# 211_MLL-Range-Extender-CAT5_v0016.net
KiCad netlist of a schematic drawn in EAGLE
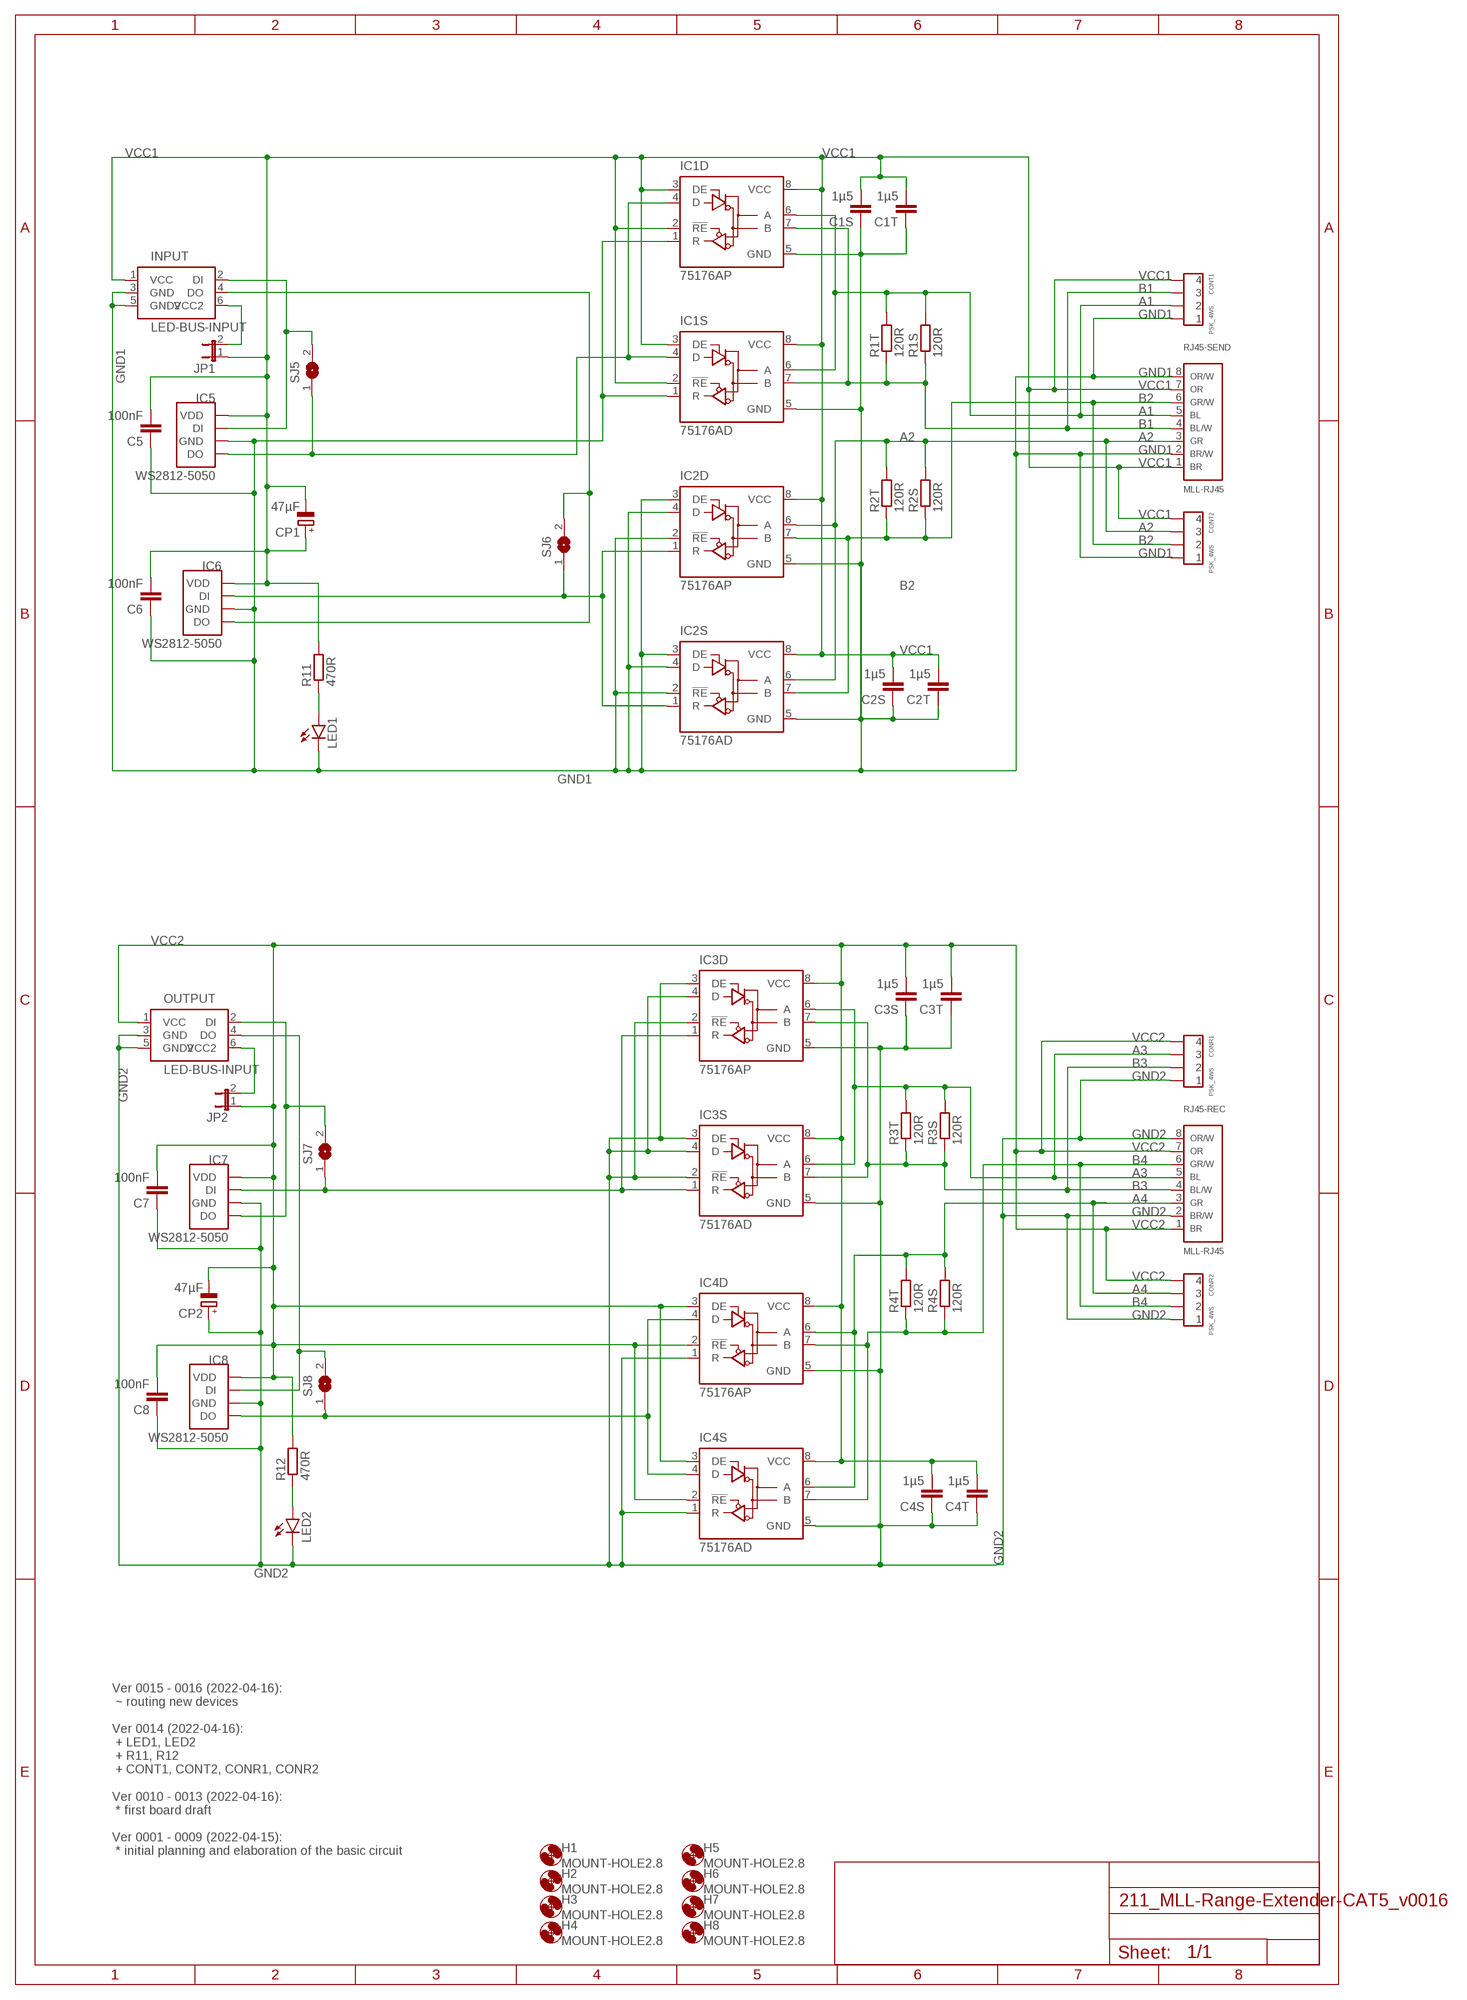
[diagram p0: schematic, sheet 1]

(export (version "E")
  (design (tool "Eeschema 10.0.6"))
  (components
    (comp (ref "C1S")
      (value "1µ5")
      (footprint "eagle-import:C1210")
      (libsource (lib "eagle-import") (part "C-EUC1210"))
    )
    (comp (ref "C1T")
      (value "1µ5")
      (footprint "eagle-import:C050-025X075")
      (libsource (lib "eagle-import") (part "C-EU050-025X075"))
    )
    (comp (ref "C2S")
      (value "1µ5")
      (footprint "eagle-import:C1210")
      (libsource (lib "eagle-import") (part "C-EUC1210"))
    )
    (comp (ref "C2T")
      (value "1µ5")
      (footprint "eagle-import:C050-025X075")
      (libsource (lib "eagle-import") (part "C-EU050-025X075"))
    )
    (comp (ref "C3S")
      (value "1µ5")
      (footprint "eagle-import:C1210")
      (libsource (lib "eagle-import") (part "C-EUC1210"))
    )
    (comp (ref "C3T")
      (value "1µ5")
      (footprint "eagle-import:C050-025X075")
      (libsource (lib "eagle-import") (part "C-EU050-025X075"))
    )
    (comp (ref "C4S")
      (value "1µ5")
      (footprint "eagle-import:C1210")
      (libsource (lib "eagle-import") (part "C-EUC1210"))
    )
    (comp (ref "C4T")
      (value "1µ5")
      (footprint "eagle-import:C050-025X075")
      (libsource (lib "eagle-import") (part "C-EU050-025X075"))
    )
    (comp (ref "C5")
      (value "100nF")
      (footprint "eagle-import:C025-025X050")
      (libsource (lib "eagle-import") (part "C-EU025-025X050"))
    )
    (comp (ref "C6")
      (value "100nF")
      (footprint "eagle-import:C025-025X050")
      (libsource (lib "eagle-import") (part "C-EU025-025X050"))
    )
    (comp (ref "C7")
      (value "100nF")
      (footprint "eagle-import:C025-025X050")
      (libsource (lib "eagle-import") (part "C-EU025-025X050"))
    )
    (comp (ref "C8")
      (value "100nF")
      (footprint "eagle-import:C025-025X050")
      (libsource (lib "eagle-import") (part "C-EU025-025X050"))
    )
    (comp (ref "CONR1")
      (value "PSK_4WS")
      (footprint "eagle-import:PSSW4-SHORT")
      (libsource (lib "eagle-import") (part "PSK_4WS"))
    )
    (comp (ref "CONR2")
      (value "PSK_4WS")
      (footprint "eagle-import:PSSW4-SHORT")
      (libsource (lib "eagle-import") (part "PSK_4WS"))
    )
    (comp (ref "CONT1")
      (value "PSK_4WS")
      (footprint "eagle-import:PSSW4-SHORT")
      (libsource (lib "eagle-import") (part "PSK_4WS"))
    )
    (comp (ref "CONT2")
      (value "PSK_4WS")
      (footprint "eagle-import:PSSW4-SHORT")
      (libsource (lib "eagle-import") (part "PSK_4WS"))
    )
    (comp (ref "CP1")
      (value "47µF")
      (footprint "eagle-import:E2-5")
      (libsource (lib "eagle-import") (part "CPOL-EUE2-5"))
    )
    (comp (ref "CP2")
      (value "47µF")
      (footprint "eagle-import:E2-5")
      (libsource (lib "eagle-import") (part "CPOL-EUE2-5"))
    )
    (comp (ref "H1")
      (value "MOUNT-HOLE2.8")
      (footprint "eagle-import:2,8")
      (libsource (lib "eagle-import") (part "MOUNT-HOLE2.8"))
    )
    (comp (ref "H2")
      (value "MOUNT-HOLE2.8")
      (footprint "eagle-import:2,8")
      (libsource (lib "eagle-import") (part "MOUNT-HOLE2.8"))
    )
    (comp (ref "H3")
      (value "MOUNT-HOLE2.8")
      (footprint "eagle-import:2,8")
      (libsource (lib "eagle-import") (part "MOUNT-HOLE2.8"))
    )
    (comp (ref "H4")
      (value "MOUNT-HOLE2.8")
      (footprint "eagle-import:2,8")
      (libsource (lib "eagle-import") (part "MOUNT-HOLE2.8"))
    )
    (comp (ref "H5")
      (value "MOUNT-HOLE2.8")
      (footprint "eagle-import:2,8")
      (libsource (lib "eagle-import") (part "MOUNT-HOLE2.8"))
    )
    (comp (ref "H6")
      (value "MOUNT-HOLE2.8")
      (footprint "eagle-import:2,8")
      (libsource (lib "eagle-import") (part "MOUNT-HOLE2.8"))
    )
    (comp (ref "H7")
      (value "MOUNT-HOLE2.8")
      (footprint "eagle-import:2,8")
      (libsource (lib "eagle-import") (part "MOUNT-HOLE2.8"))
    )
    (comp (ref "H8")
      (value "MOUNT-HOLE2.8")
      (footprint "eagle-import:2,8")
      (libsource (lib "eagle-import") (part "MOUNT-HOLE2.8"))
    )
    (comp (ref "IC1D")
      (value "75176AP")
      (footprint "eagle-import:DIL08")
      (libsource (lib "eagle-import") (part "75176AP"))
    )
    (comp (ref "IC1S")
      (value "75176AD")
      (footprint "eagle-import:D_R-PDSO-G8")
      (libsource (lib "eagle-import") (part "75176AD"))
    )
    (comp (ref "IC2D")
      (value "75176AP")
      (footprint "eagle-import:DIL08")
      (libsource (lib "eagle-import") (part "75176AP"))
    )
    (comp (ref "IC2S")
      (value "75176AD")
      (footprint "eagle-import:D_R-PDSO-G8")
      (libsource (lib "eagle-import") (part "75176AD"))
    )
    (comp (ref "IC3D")
      (value "75176AP")
      (footprint "eagle-import:DIL08")
      (libsource (lib "eagle-import") (part "75176AP"))
    )
    (comp (ref "IC3S")
      (value "75176AD")
      (footprint "eagle-import:D_R-PDSO-G8")
      (libsource (lib "eagle-import") (part "75176AD"))
    )
    (comp (ref "IC4D")
      (value "75176AP")
      (footprint "eagle-import:DIL08")
      (libsource (lib "eagle-import") (part "75176AP"))
    )
    (comp (ref "IC4S")
      (value "75176AD")
      (footprint "eagle-import:D_R-PDSO-G8")
      (libsource (lib "eagle-import") (part "75176AD"))
    )
    (comp (ref "IC5")
      (value "WS2812-5050")
      (footprint "eagle-import:5050")
      (libsource (lib "eagle-import") (part "WS2812-5050"))
    )
    (comp (ref "IC6")
      (value "WS2812-5050")
      (footprint "eagle-import:5050")
      (libsource (lib "eagle-import") (part "WS2812-5050"))
    )
    (comp (ref "IC7")
      (value "WS2812-5050")
      (footprint "eagle-import:5050")
      (libsource (lib "eagle-import") (part "WS2812-5050"))
    )
    (comp (ref "IC8")
      (value "WS2812-5050")
      (footprint "eagle-import:5050")
      (libsource (lib "eagle-import") (part "WS2812-5050"))
    )
    (comp (ref "INPUT")
      (value "LED-BUS-INPUT")
      (footprint "eagle-import:IDC6")
      (libsource (lib "eagle-import") (part "LED-BUS-INPUT"))
    )
    (comp (ref "JP1")
      (value "JP1E")
      (footprint "eagle-import:JP1")
      (libsource (lib "eagle-import") (part "JP1E"))
    )
    (comp (ref "JP2")
      (value "JP1E")
      (footprint "eagle-import:JP1")
      (libsource (lib "eagle-import") (part "JP1E"))
    )
    (comp (ref "LED1")
      (value "LED3MM")
      (footprint "eagle-import:LED3MM")
      (libsource (lib "eagle-import") (part "LED3MM"))
    )
    (comp (ref "LED2")
      (value "LED3MM")
      (footprint "eagle-import:LED3MM")
      (libsource (lib "eagle-import") (part "LED3MM"))
    )
    (comp (ref "OUTPUT")
      (value "LED-BUS-INPUT")
      (footprint "eagle-import:IDC6")
      (libsource (lib "eagle-import") (part "LED-BUS-INPUT"))
    )
    (comp (ref "R1S")
      (value "120R")
      (footprint "eagle-import:R1210")
      (libsource (lib "eagle-import") (part "R-EU_R1210"))
    )
    (comp (ref "R1T")
      (value "120R")
      (footprint "eagle-import:0207_10")
      (libsource (lib "eagle-import") (part "R-EU_0207/10"))
    )
    (comp (ref "R2S")
      (value "120R")
      (footprint "eagle-import:R1210")
      (libsource (lib "eagle-import") (part "R-EU_R1210"))
    )
    (comp (ref "R2T")
      (value "120R")
      (footprint "eagle-import:0207_10")
      (libsource (lib "eagle-import") (part "R-EU_0207/10"))
    )
    (comp (ref "R3S")
      (value "120R")
      (footprint "eagle-import:R1210")
      (libsource (lib "eagle-import") (part "R-EU_R1210"))
    )
    (comp (ref "R3T")
      (value "120R")
      (footprint "eagle-import:0207_10")
      (libsource (lib "eagle-import") (part "R-EU_0207/10"))
    )
    (comp (ref "R4S")
      (value "120R")
      (footprint "eagle-import:R1210")
      (libsource (lib "eagle-import") (part "R-EU_R1210"))
    )
    (comp (ref "R4T")
      (value "120R")
      (footprint "eagle-import:0207_10")
      (libsource (lib "eagle-import") (part "R-EU_0207/10"))
    )
    (comp (ref "R11")
      (value "470R")
      (footprint "eagle-import:0207_10")
      (libsource (lib "eagle-import") (part "R-EU_0207/10"))
    )
    (comp (ref "R12")
      (value "470R")
      (footprint "eagle-import:0207_10")
      (libsource (lib "eagle-import") (part "R-EU_0207/10"))
    )
    (comp (ref "RJ45-REC")
      (value "MLL-RJ45")
      (footprint "eagle-import:RJ45_U")
      (libsource (lib "eagle-import") (part "MLL-RJ45"))
    )
    (comp (ref "RJ45-SEND")
      (value "MLL-RJ45")
      (footprint "eagle-import:RJ45_U")
      (libsource (lib "eagle-import") (part "MLL-RJ45"))
    )
    (comp (ref "SJ5") (value "SJ") (footprint "eagle-import:SJ") (libsource (lib "eagle-import") (part "SJ")))
    (comp (ref "SJ6") (value "SJ") (footprint "eagle-import:SJ") (libsource (lib "eagle-import") (part "SJ")))
    (comp (ref "SJ7") (value "SJ") (footprint "eagle-import:SJ") (libsource (lib "eagle-import") (part "SJ")))
    (comp (ref "SJ8") (value "SJ") (footprint "eagle-import:SJ") (libsource (lib "eagle-import") (part "SJ")))
  )
  (nets
    (net (code "1") (name "/A1") (class "Default")
      (node (ref "CONT1") (pin "P$2") (pinfunction "2_P$2") (pintype "bidirectional"))
      (node (ref "IC1D") (pin "6") (pinfunction "A_6") (pintype "output"))
      (node (ref "IC1S") (pin "6") (pinfunction "A_6") (pintype "output"))
      (node (ref "R1S") (pin "2") (pinfunction "2_2") (pintype "passive"))
      (node (ref "R1T") (pin "2") (pinfunction "2_2") (pintype "passive"))
      (node (ref "RJ45-SEND") (pin "5") (pinfunction "BLUE_5") (pintype "bidirectional"))
    )
    (net (code "2") (name "/A2") (class "Default")
      (node (ref "CONT2") (pin "P$3") (pinfunction "3_P$3") (pintype "bidirectional"))
      (node (ref "IC2D") (pin "6") (pinfunction "A_6") (pintype "output"))
      (node (ref "IC2S") (pin "6") (pinfunction "A_6") (pintype "output"))
      (node (ref "R2S") (pin "2") (pinfunction "2_2") (pintype "passive"))
      (node (ref "R2T") (pin "2") (pinfunction "2_2") (pintype "passive"))
      (node (ref "RJ45-SEND") (pin "3") (pinfunction "GREEN_3") (pintype "bidirectional"))
    )
    (net (code "3") (name "/A3") (class "Default")
      (node (ref "CONR1") (pin "P$3") (pinfunction "3_P$3") (pintype "bidirectional"))
      (node (ref "IC3D") (pin "6") (pinfunction "A_6") (pintype "output"))
      (node (ref "IC3S") (pin "6") (pinfunction "A_6") (pintype "output"))
      (node (ref "R3S") (pin "2") (pinfunction "2_2") (pintype "passive"))
      (node (ref "R3T") (pin "2") (pinfunction "2_2") (pintype "passive"))
      (node (ref "RJ45-REC") (pin "5") (pinfunction "BLUE_5") (pintype "bidirectional"))
    )
    (net (code "4") (name "/A4") (class "Default")
      (node (ref "CONR2") (pin "P$3") (pinfunction "3_P$3") (pintype "bidirectional"))
      (node (ref "IC4D") (pin "6") (pinfunction "A_6") (pintype "output"))
      (node (ref "IC4S") (pin "6") (pinfunction "A_6") (pintype "output"))
      (node (ref "R4S") (pin "2") (pinfunction "2_2") (pintype "passive"))
      (node (ref "R4T") (pin "2") (pinfunction "2_2") (pintype "passive"))
      (node (ref "RJ45-REC") (pin "3") (pinfunction "GREEN_3") (pintype "bidirectional"))
    )
    (net (code "5") (name "/B1") (class "Default")
      (node (ref "CONT1") (pin "P$3") (pinfunction "3_P$3") (pintype "bidirectional"))
      (node (ref "IC1D") (pin "7") (pinfunction "B_7") (pintype "output"))
      (node (ref "IC1S") (pin "7") (pinfunction "B_7") (pintype "output"))
      (node (ref "R1S") (pin "1") (pinfunction "1_1") (pintype "passive"))
      (node (ref "R1T") (pin "1") (pinfunction "1_1") (pintype "passive"))
      (node (ref "RJ45-SEND") (pin "4") (pinfunction "BLUE/WHITE_4") (pintype "bidirectional"))
    )
    (net (code "6") (name "/B2") (class "Default")
      (node (ref "CONT2") (pin "P$2") (pinfunction "2_P$2") (pintype "bidirectional"))
      (node (ref "IC2D") (pin "7") (pinfunction "B_7") (pintype "output"))
      (node (ref "IC2S") (pin "7") (pinfunction "B_7") (pintype "output"))
      (node (ref "R2S") (pin "1") (pinfunction "1_1") (pintype "passive"))
      (node (ref "R2T") (pin "1") (pinfunction "1_1") (pintype "passive"))
      (node (ref "RJ45-SEND") (pin "6") (pinfunction "GREEN/WHITE_6") (pintype "bidirectional"))
    )
    (net (code "7") (name "/B3") (class "Default")
      (node (ref "CONR1") (pin "P$2") (pinfunction "2_P$2") (pintype "bidirectional"))
      (node (ref "IC3D") (pin "7") (pinfunction "B_7") (pintype "output"))
      (node (ref "IC3S") (pin "7") (pinfunction "B_7") (pintype "output"))
      (node (ref "R3S") (pin "1") (pinfunction "1_1") (pintype "passive"))
      (node (ref "R3T") (pin "1") (pinfunction "1_1") (pintype "passive"))
      (node (ref "RJ45-REC") (pin "4") (pinfunction "BLUE/WHITE_4") (pintype "bidirectional"))
    )
    (net (code "8") (name "/B4") (class "Default")
      (node (ref "CONR2") (pin "P$2") (pinfunction "2_P$2") (pintype "bidirectional"))
      (node (ref "IC4D") (pin "7") (pinfunction "B_7") (pintype "output"))
      (node (ref "IC4S") (pin "7") (pinfunction "B_7") (pintype "output"))
      (node (ref "R4S") (pin "1") (pinfunction "1_1") (pintype "passive"))
      (node (ref "R4T") (pin "1") (pinfunction "1_1") (pintype "passive"))
      (node (ref "RJ45-REC") (pin "6") (pinfunction "GREEN/WHITE_6") (pintype "bidirectional"))
    )
    (net (code "9") (name "/GND1") (class "Default")
      (node (ref "C1S") (pin "1") (pinfunction "1_1") (pintype "passive"))
      (node (ref "C1T") (pin "1") (pinfunction "1_1") (pintype "passive"))
      (node (ref "C2S") (pin "1") (pinfunction "1_1") (pintype "passive"))
      (node (ref "C2T") (pin "1") (pinfunction "1_1") (pintype "passive"))
      (node (ref "C5") (pin "1") (pinfunction "1_1") (pintype "passive"))
      (node (ref "C6") (pin "1") (pinfunction "1_1") (pintype "passive"))
      (node (ref "CONT1") (pin "P$1") (pinfunction "1_P$1") (pintype "bidirectional"))
      (node (ref "CONT2") (pin "P$1") (pinfunction "1_P$1") (pintype "bidirectional"))
      (node (ref "IC1D") (pin "1") (pinfunction "R_1") (pintype "input"))
      (node (ref "IC1D") (pin "5") (pinfunction "GND_5") (pintype "power_in"))
      (node (ref "IC1S") (pin "1") (pinfunction "R_1") (pintype "input"))
      (node (ref "IC1S") (pin "5") (pinfunction "GND_5") (pintype "power_in"))
      (node (ref "IC2D") (pin "2") (pinfunction "~{RE}_2") (pintype "input"))
      (node (ref "IC2D") (pin "3") (pinfunction "DE_3") (pintype "input"))
      (node (ref "IC2D") (pin "4") (pinfunction "D_4") (pintype "input"))
      (node (ref "IC2D") (pin "5") (pinfunction "GND_5") (pintype "power_in"))
      (node (ref "IC2S") (pin "2") (pinfunction "~{RE}_2") (pintype "input"))
      (node (ref "IC2S") (pin "3") (pinfunction "DE_3") (pintype "input"))
      (node (ref "IC2S") (pin "4") (pinfunction "D_4") (pintype "input"))
      (node (ref "IC2S") (pin "5") (pinfunction "GND_5") (pintype "power_in"))
      (node (ref "IC5") (pin "GND") (pinfunction "GND_GND") (pintype "power_in"))
      (node (ref "IC6") (pin "GND") (pinfunction "GND_GND") (pintype "power_in"))
      (node (ref "INPUT") (pin "3") (pinfunction "GND_3") (pintype "power_in"))
      (node (ref "INPUT") (pin "5") (pinfunction "GND2_5") (pintype "power_in"))
      (node (ref "LED1") (pin "K") (pinfunction "C_K") (pintype "passive"))
      (node (ref "RJ45-SEND") (pin "2") (pinfunction "BROWN/WHITE_2") (pintype "bidirectional"))
      (node (ref "RJ45-SEND") (pin "8") (pinfunction "ORANGE/WHITE_8") (pintype "bidirectional"))
    )
    (net (code "10") (name "/GND2") (class "Default")
      (node (ref "C3S") (pin "1") (pinfunction "1_1") (pintype "passive"))
      (node (ref "C3T") (pin "1") (pinfunction "1_1") (pintype "passive"))
      (node (ref "C4S") (pin "1") (pinfunction "1_1") (pintype "passive"))
      (node (ref "C4T") (pin "1") (pinfunction "1_1") (pintype "passive"))
      (node (ref "C7") (pin "1") (pinfunction "1_1") (pintype "passive"))
      (node (ref "C8") (pin "1") (pinfunction "1_1") (pintype "passive"))
      (node (ref "CONR1") (pin "P$1") (pinfunction "1_P$1") (pintype "bidirectional"))
      (node (ref "CONR2") (pin "P$1") (pinfunction "1_P$1") (pintype "bidirectional"))
      (node (ref "CP2") (pin "+") (pinfunction "+_+") (pintype "passive"))
      (node (ref "IC3D") (pin "2") (pinfunction "~{RE}_2") (pintype "input"))
      (node (ref "IC3D") (pin "3") (pinfunction "DE_3") (pintype "input"))
      (node (ref "IC3D") (pin "4") (pinfunction "D_4") (pintype "input"))
      (node (ref "IC3D") (pin "5") (pinfunction "GND_5") (pintype "power_in"))
      (node (ref "IC3S") (pin "2") (pinfunction "~{RE}_2") (pintype "input"))
      (node (ref "IC3S") (pin "3") (pinfunction "DE_3") (pintype "input"))
      (node (ref "IC3S") (pin "4") (pinfunction "D_4") (pintype "input"))
      (node (ref "IC3S") (pin "5") (pinfunction "GND_5") (pintype "power_in"))
      (node (ref "IC4D") (pin "1") (pinfunction "R_1") (pintype "input"))
      (node (ref "IC4D") (pin "5") (pinfunction "GND_5") (pintype "power_in"))
      (node (ref "IC4S") (pin "1") (pinfunction "R_1") (pintype "input"))
      (node (ref "IC4S") (pin "5") (pinfunction "GND_5") (pintype "power_in"))
      (node (ref "IC7") (pin "GND") (pinfunction "GND_GND") (pintype "power_in"))
      (node (ref "IC8") (pin "GND") (pinfunction "GND_GND") (pintype "power_in"))
      (node (ref "LED2") (pin "K") (pinfunction "C_K") (pintype "passive"))
      (node (ref "OUTPUT") (pin "3") (pinfunction "GND_3") (pintype "power_in"))
      (node (ref "OUTPUT") (pin "5") (pinfunction "GND2_5") (pintype "power_in"))
      (node (ref "RJ45-REC") (pin "2") (pinfunction "BROWN/WHITE_2") (pintype "bidirectional"))
      (node (ref "RJ45-REC") (pin "8") (pinfunction "ORANGE/WHITE_8") (pintype "bidirectional"))
    )
    (net (code "11") (name "/VCC1") (class "Default")
      (node (ref "C1S") (pin "2") (pinfunction "2_2") (pintype "passive"))
      (node (ref "C1T") (pin "2") (pinfunction "2_2") (pintype "passive"))
      (node (ref "C2S") (pin "2") (pinfunction "2_2") (pintype "passive"))
      (node (ref "C2T") (pin "2") (pinfunction "2_2") (pintype "passive"))
      (node (ref "C5") (pin "2") (pinfunction "2_2") (pintype "passive"))
      (node (ref "C6") (pin "2") (pinfunction "2_2") (pintype "passive"))
      (node (ref "CONT1") (pin "P$4") (pinfunction "4_P$4") (pintype "bidirectional"))
      (node (ref "CONT2") (pin "P$4") (pinfunction "4_P$4") (pintype "bidirectional"))
      (node (ref "CP1") (pin "+") (pinfunction "+_+") (pintype "passive"))
      (node (ref "CP1") (pin "-") (pinfunction "-_-") (pintype "passive"))
      (node (ref "IC1D") (pin "2") (pinfunction "~{RE}_2") (pintype "input"))
      (node (ref "IC1D") (pin "3") (pinfunction "DE_3") (pintype "input"))
      (node (ref "IC1D") (pin "8") (pinfunction "VCC_8") (pintype "power_in"))
      (node (ref "IC1S") (pin "2") (pinfunction "~{RE}_2") (pintype "input"))
      (node (ref "IC1S") (pin "3") (pinfunction "DE_3") (pintype "input"))
      (node (ref "IC1S") (pin "8") (pinfunction "VCC_8") (pintype "power_in"))
      (node (ref "IC2D") (pin "8") (pinfunction "VCC_8") (pintype "power_in"))
      (node (ref "IC2S") (pin "8") (pinfunction "VCC_8") (pintype "power_in"))
      (node (ref "IC5") (pin "VCC") (pinfunction "VDD_VCC") (pintype "power_in"))
      (node (ref "IC6") (pin "VCC") (pinfunction "VDD_VCC") (pintype "power_in"))
      (node (ref "INPUT") (pin "1") (pinfunction "VCC_1") (pintype "power_in"))
      (node (ref "JP1") (pin "1") (pinfunction "1_1") (pintype "passive"))
      (node (ref "R11") (pin "2") (pinfunction "2_2") (pintype "passive"))
      (node (ref "RJ45-SEND") (pin "1") (pinfunction "BROWN_1") (pintype "bidirectional"))
      (node (ref "RJ45-SEND") (pin "7") (pinfunction "OPRANGE_7") (pintype "bidirectional"))
    )
    (net (code "12") (name "/VCC2") (class "Default")
      (node (ref "C3S") (pin "2") (pinfunction "2_2") (pintype "passive"))
      (node (ref "C3T") (pin "2") (pinfunction "2_2") (pintype "passive"))
      (node (ref "C4S") (pin "2") (pinfunction "2_2") (pintype "passive"))
      (node (ref "C4T") (pin "2") (pinfunction "2_2") (pintype "passive"))
      (node (ref "C7") (pin "2") (pinfunction "2_2") (pintype "passive"))
      (node (ref "C8") (pin "2") (pinfunction "2_2") (pintype "passive"))
      (node (ref "CONR1") (pin "P$4") (pinfunction "4_P$4") (pintype "bidirectional"))
      (node (ref "CONR2") (pin "P$4") (pinfunction "4_P$4") (pintype "bidirectional"))
      (node (ref "CP2") (pin "-") (pinfunction "-_-") (pintype "passive"))
      (node (ref "IC3D") (pin "8") (pinfunction "VCC_8") (pintype "power_in"))
      (node (ref "IC3S") (pin "8") (pinfunction "VCC_8") (pintype "power_in"))
      (node (ref "IC4D") (pin "2") (pinfunction "~{RE}_2") (pintype "input"))
      (node (ref "IC4D") (pin "3") (pinfunction "DE_3") (pintype "input"))
      (node (ref "IC4D") (pin "8") (pinfunction "VCC_8") (pintype "power_in"))
      (node (ref "IC4S") (pin "2") (pinfunction "~{RE}_2") (pintype "input"))
      (node (ref "IC4S") (pin "3") (pinfunction "DE_3") (pintype "input"))
      (node (ref "IC4S") (pin "8") (pinfunction "VCC_8") (pintype "power_in"))
      (node (ref "IC7") (pin "VCC") (pinfunction "VDD_VCC") (pintype "power_in"))
      (node (ref "IC8") (pin "VCC") (pinfunction "VDD_VCC") (pintype "power_in"))
      (node (ref "JP2") (pin "1") (pinfunction "1_1") (pintype "passive"))
      (node (ref "OUTPUT") (pin "1") (pinfunction "VCC_1") (pintype "power_in"))
      (node (ref "R12") (pin "2") (pinfunction "2_2") (pintype "passive"))
      (node (ref "RJ45-REC") (pin "1") (pinfunction "BROWN_1") (pintype "bidirectional"))
      (node (ref "RJ45-REC") (pin "7") (pinfunction "OPRANGE_7") (pintype "bidirectional"))
    )
    (net (code "13") (name "Net-(IC1D-D)") (class "Default")
      (node (ref "IC1D") (pin "4") (pinfunction "D_4") (pintype "input"))
      (node (ref "IC1S") (pin "4") (pinfunction "D_4") (pintype "input"))
      (node (ref "IC5") (pin "DO") (pinfunction "DO_DO") (pintype "output"))
      (node (ref "SJ5") (pin "1") (pinfunction "1_1") (pintype "passive"))
    )
    (net (code "14") (name "Net-(IC2D-R)") (class "Default")
      (node (ref "IC2D") (pin "1") (pinfunction "R_1") (pintype "input"))
      (node (ref "IC2S") (pin "1") (pinfunction "R_1") (pintype "input"))
      (node (ref "IC6") (pin "DI") (pinfunction "DI_DI") (pintype "input"))
      (node (ref "SJ6") (pin "1") (pinfunction "1_1") (pintype "passive"))
    )
    (net (code "15") (name "Net-(IC3D-R)") (class "Default")
      (node (ref "IC3D") (pin "1") (pinfunction "R_1") (pintype "input"))
      (node (ref "IC3S") (pin "1") (pinfunction "R_1") (pintype "input"))
      (node (ref "IC7") (pin "DI") (pinfunction "DI_DI") (pintype "input"))
      (node (ref "SJ7") (pin "1") (pinfunction "1_1") (pintype "passive"))
    )
    (net (code "16") (name "Net-(IC4D-D)") (class "Default")
      (node (ref "IC4D") (pin "4") (pinfunction "D_4") (pintype "input"))
      (node (ref "IC4S") (pin "4") (pinfunction "D_4") (pintype "input"))
      (node (ref "IC8") (pin "DO") (pinfunction "DO_DO") (pintype "output"))
      (node (ref "SJ8") (pin "1") (pinfunction "1_1") (pintype "passive"))
    )
    (net (code "17") (name "Net-(INPUT-DI)") (class "Default")
      (node (ref "IC5") (pin "DI") (pinfunction "DI_DI") (pintype "input"))
      (node (ref "INPUT") (pin "2") (pinfunction "DI_2") (pintype "input"))
      (node (ref "SJ5") (pin "2") (pinfunction "2_2") (pintype "passive"))
    )
    (net (code "18") (name "Net-(INPUT-DO)") (class "Default")
      (node (ref "IC6") (pin "DO") (pinfunction "DO_DO") (pintype "output"))
      (node (ref "INPUT") (pin "4") (pinfunction "DO_4") (pintype "output"))
      (node (ref "SJ6") (pin "2") (pinfunction "2_2") (pintype "passive"))
    )
    (net (code "19") (name "Net-(INPUT-VCC2)") (class "Default")
      (node (ref "INPUT") (pin "6") (pinfunction "VCC2_6") (pintype "power_in"))
      (node (ref "JP1") (pin "2") (pinfunction "2_2") (pintype "passive"))
    )
    (net (code "20") (name "Net-(LED1-PadA)") (class "Default")
      (node (ref "LED1") (pin "A") (pinfunction "A_A") (pintype "passive"))
      (node (ref "R11") (pin "1") (pinfunction "1_1") (pintype "passive"))
    )
    (net (code "21") (name "Net-(LED2-PadA)") (class "Default")
      (node (ref "LED2") (pin "A") (pinfunction "A_A") (pintype "passive"))
      (node (ref "R12") (pin "1") (pinfunction "1_1") (pintype "passive"))
    )
    (net (code "22") (name "Net-(OUTPUT-DI)") (class "Default")
      (node (ref "IC7") (pin "DO") (pinfunction "DO_DO") (pintype "output"))
      (node (ref "OUTPUT") (pin "2") (pinfunction "DI_2") (pintype "input"))
      (node (ref "SJ7") (pin "2") (pinfunction "2_2") (pintype "passive"))
    )
    (net (code "23") (name "Net-(OUTPUT-DO)") (class "Default")
      (node (ref "IC8") (pin "DI") (pinfunction "DI_DI") (pintype "input"))
      (node (ref "OUTPUT") (pin "4") (pinfunction "DO_4") (pintype "output"))
      (node (ref "SJ8") (pin "2") (pinfunction "2_2") (pintype "passive"))
    )
    (net (code "24") (name "Net-(OUTPUT-VCC2)") (class "Default")
      (node (ref "JP2") (pin "2") (pinfunction "2_2") (pintype "passive"))
      (node (ref "OUTPUT") (pin "6") (pinfunction "VCC2_6") (pintype "power_in"))
    )
  )
)
